# ASM2021.net
KiCad netlist of a schematic drawn in EAGLE
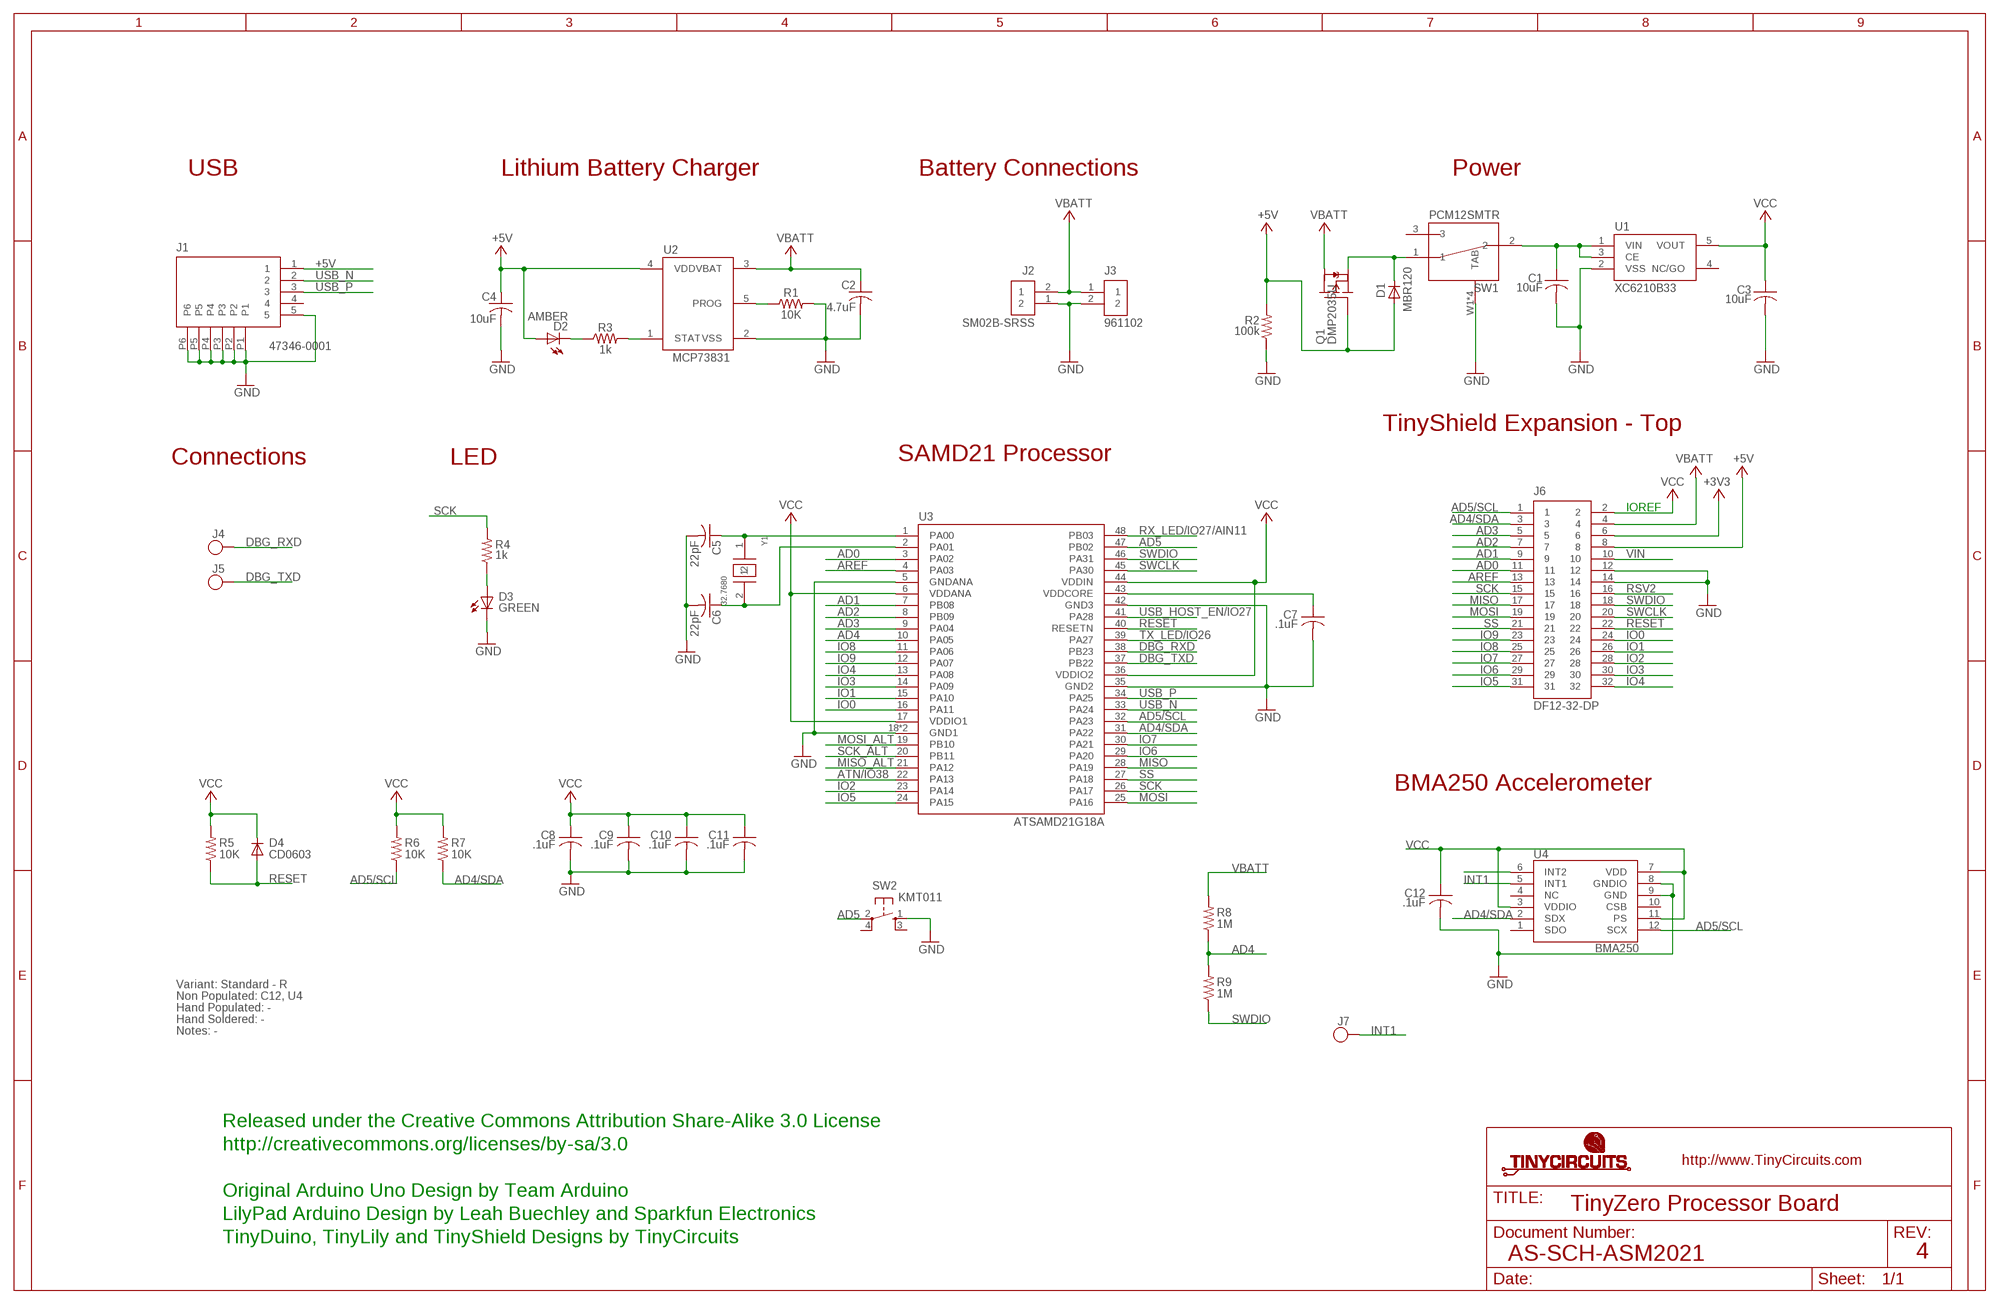
[diagram p0: schematic, sheet 1]

(export (version "E")
  (design (tool "Eeschema 10.0.6"))
  (components
    (comp (ref "C1")
      (value "10uF")
      (footprint "eagle-import:C0603")
      (fields (field (name "PARTNO") "AS-ITM-00002") (field (name "PARTNO_1") "AS-ITM-00002"))
      (libsource (lib "eagle-import") (part "AS-ITM-00002"))
    )
    (comp (ref "C2")
      (value "4.7uF")
      (footprint "eagle-import:C0603")
      (fields (field (name "PARTNO") "AS-ITM-00088") (field (name "PARTNO_1") "AS-ITM-00088"))
      (libsource (lib "eagle-import") (part "AS-ITM-00088"))
    )
    (comp (ref "C3")
      (value "10uF")
      (footprint "eagle-import:C0603")
      (fields (field (name "PARTNO") "AS-ITM-00002") (field (name "PARTNO_1") "AS-ITM-00002"))
      (libsource (lib "eagle-import") (part "AS-ITM-00002"))
    )
    (comp (ref "C4")
      (value "10uF")
      (footprint "eagle-import:C0603")
      (fields (field (name "PARTNO") "AS-ITM-00002") (field (name "PARTNO_1") "AS-ITM-00002"))
      (libsource (lib "eagle-import") (part "AS-ITM-00002"))
    )
    (comp (ref "C5")
      (value "22pF")
      (footprint "eagle-import:C0402")
      (fields (field (name "PARTNO") "AS-ITM-00211") (field (name "PARTNO_1") "AS-ITM-00211"))
      (libsource (lib "eagle-import") (part "AS-ITM-00211"))
    )
    (comp (ref "C6")
      (value "22pF")
      (footprint "eagle-import:C0402")
      (fields (field (name "PARTNO") "AS-ITM-00211") (field (name "PARTNO_1") "AS-ITM-00211"))
      (libsource (lib "eagle-import") (part "AS-ITM-00211"))
    )
    (comp (ref "C7")
      (value ".1uF")
      (footprint "eagle-import:C0402")
      (fields (field (name "PARTNO") "AS-ITM-00008") (field (name "PARTNO_1") "AS-ITM-00008"))
      (libsource (lib "eagle-import") (part "AS-ITM-00008"))
    )
    (comp (ref "C8")
      (value ".1uF")
      (footprint "eagle-import:C0402")
      (fields (field (name "PARTNO") "AS-ITM-00008") (field (name "PARTNO_1") "AS-ITM-00008"))
      (libsource (lib "eagle-import") (part "AS-ITM-00008"))
    )
    (comp (ref "C9")
      (value ".1uF")
      (footprint "eagle-import:C0402")
      (fields (field (name "PARTNO") "AS-ITM-00008") (field (name "PARTNO_1") "AS-ITM-00008"))
      (libsource (lib "eagle-import") (part "AS-ITM-00008"))
    )
    (comp (ref "C10")
      (value ".1uF")
      (footprint "eagle-import:C0402")
      (fields (field (name "PARTNO") "AS-ITM-00008") (field (name "PARTNO_1") "AS-ITM-00008"))
      (libsource (lib "eagle-import") (part "AS-ITM-00008"))
    )
    (comp (ref "C11")
      (value ".1uF")
      (footprint "eagle-import:C0402")
      (fields (field (name "PARTNO") "AS-ITM-00008") (field (name "PARTNO_1") "AS-ITM-00008"))
      (libsource (lib "eagle-import") (part "AS-ITM-00008"))
    )
    (comp (ref "C12")
      (value ".1uF")
      (footprint "eagle-import:C0402")
      (fields (field (name "PARTNO") "AS-ITM-00008") (field (name "PARTNO_1") "AS-ITM-00008"))
      (libsource (lib "eagle-import") (part "AS-ITM-00008"))
    )
    (comp (ref "D1")
      (value "MBR120")
      (footprint "eagle-import:SOD-123FL")
      (fields (field (name "PARTNO") "AS-ITM-00111"))
      (libsource (lib "eagle-import") (part "AS-ITM-00111"))
    )
    (comp (ref "D2")
      (value "AMBER")
      (footprint "eagle-import:LNJ_LED")
      (fields (field (name "PARTNO") "AS-ITM-00026") (field (name "PARTNO_1") "AS-ITM-00026"))
      (libsource (lib "eagle-import") (part "AS-ITM-00026"))
    )
    (comp (ref "D3")
      (value "GREEN")
      (footprint "eagle-import:LNJ_LED")
      (fields (field (name "PARTNO") "AS-ITM-00011") (field (name "PARTNO_1") "AS-ITM-00011"))
      (libsource (lib "eagle-import") (part "AS-ITM-00011"))
    )
    (comp (ref "D4")
      (value "CD0603")
      (footprint "eagle-import:0603")
      (fields (field (name "PARTNO") "AS-ITM-00009") (field (name "PARTNO_1") "AS-ITM-00009"))
      (libsource (lib "eagle-import") (part "AS-ITM-00009"))
    )
    (comp (ref "J1")
      (value "47346-0001")
      (footprint "eagle-import:MICRO_USB")
      (fields (field (name "PARTNO") "AS-ITM-00021"))
      (libsource (lib "eagle-import") (part "AS-ITM-00021"))
    )
    (comp (ref "J2")
      (value "SM02B-SRSS")
      (footprint "eagle-import:JST_SH_2X1")
      (fields (field (name "PARTNO") "AS-ITM-00231"))
      (libsource (lib "eagle-import") (part "AS-ITM-00231"))
    )
    (comp (ref "J3")
      (value "961102")
      (footprint "eagle-import:2X.1_")
      (fields (field (name "PARTNO") "AS-ITM-00044"))
      (libsource (lib "eagle-import") (part "AS-ITM-00044"))
    )
    (comp (ref "J4")
      (value "TEST_POINT")
      (footprint "eagle-import:TEST_POINT_1MM")
      (libsource (lib "eagle-import") (part "TEST_POINT"))
    )
    (comp (ref "J5")
      (value "TEST_POINT")
      (footprint "eagle-import:TEST_POINT_1MM")
      (libsource (lib "eagle-import") (part "TEST_POINT"))
    )
    (comp (ref "J6")
      (value "DF12-32-DP")
      (footprint "eagle-import:DF12-32-DP")
      (fields (field (name "PARTNO") "AS-ITM-00015") (field (name "PARTNO_1") "AS-ITM-00015"))
      (libsource (lib "eagle-import") (part "AS-ITM-00015"))
    )
    (comp (ref "J7")
      (value "TEST_POINT")
      (footprint "eagle-import:TEST_POINT_1MM")
      (libsource (lib "eagle-import") (part "TEST_POINT"))
    )
    (comp (ref "Q1")
      (value "DMP2035U")
      (footprint "eagle-import:SOT23")
      (fields (field (name "PARTNO") "AS-ITM-00024"))
      (libsource (lib "eagle-import") (part "AS-ITM-00024"))
    )
    (comp (ref "R1")
      (value "10K")
      (footprint "eagle-import:0402")
      (fields (field (name "PARTNO") "AS-ITM-00032"))
      (libsource (lib "eagle-import") (part "AS-ITM-00032"))
    )
    (comp (ref "R2")
      (value "100k")
      (footprint "eagle-import:0402")
      (fields (field (name "PARTNO") "AS-ITM-00004") (field (name "PARTNO_1") "AS-ITM-00004"))
      (libsource (lib "eagle-import") (part "AS-ITM-00004"))
    )
    (comp (ref "R3")
      (value "1k")
      (footprint "eagle-import:0402")
      (fields (field (name "PARTNO") "AS-ITM-00003") (field (name "PARTNO_1") "AS-ITM-00003"))
      (libsource (lib "eagle-import") (part "AS-ITM-00003"))
    )
    (comp (ref "R4")
      (value "1k")
      (footprint "eagle-import:0402")
      (fields (field (name "PARTNO") "AS-ITM-00003") (field (name "PARTNO_1") "AS-ITM-00003"))
      (libsource (lib "eagle-import") (part "AS-ITM-00003"))
    )
    (comp (ref "R5")
      (value "10K")
      (footprint "eagle-import:0402")
      (fields (field (name "PARTNO") "AS-ITM-00032") (field (name "PARTNO_1") "AS-ITM-00032"))
      (libsource (lib "eagle-import") (part "AS-ITM-00032"))
    )
    (comp (ref "R6")
      (value "10K")
      (footprint "eagle-import:0402")
      (fields (field (name "PARTNO") "AS-ITM-00032") (field (name "PARTNO_1") "AS-ITM-00032"))
      (libsource (lib "eagle-import") (part "AS-ITM-00032"))
    )
    (comp (ref "R7")
      (value "10K")
      (footprint "eagle-import:0402")
      (fields (field (name "PARTNO") "AS-ITM-00032") (field (name "PARTNO_1") "AS-ITM-00032"))
      (libsource (lib "eagle-import") (part "AS-ITM-00032"))
    )
    (comp (ref "R8")
      (value "1M")
      (footprint "eagle-import:0402")
      (fields (field (name "PARTNO") "AS-ITM-00005") (field (name "PARTNO_1") "AS-ITM-00005"))
      (libsource (lib "eagle-import") (part "AS-ITM-00005"))
    )
    (comp (ref "R9")
      (value "1M")
      (footprint "eagle-import:0402")
      (fields (field (name "PARTNO") "AS-ITM-00005") (field (name "PARTNO_1") "AS-ITM-00005"))
      (libsource (lib "eagle-import") (part "AS-ITM-00005"))
    )
    (comp (ref "SW1")
      (value "PCM12SMTR")
      (footprint "eagle-import:PCM12SMTR")
      (fields (field (name "PARTNO") "AS-ITM-00220"))
      (libsource (lib "eagle-import") (part "AS-ITM-00220"))
    )
    (comp (ref "SW2")
      (value "KMT011")
      (footprint "eagle-import:KMT011")
      (fields (field (name "PARTNO") "AS-ITM-00041"))
      (libsource (lib "eagle-import") (part "AS-ITM-00041"))
    )
    (comp (ref "U1")
      (value "XC6210B33")
      (footprint "eagle-import:SOT-25")
      (fields (field (name "PARTNO") "AS-ITM-00046"))
      (libsource (lib "eagle-import") (part "AS-ITM-00046"))
    )
    (comp (ref "U2")
      (value "MCP73831")
      (footprint "eagle-import:SOT-23")
      (fields (field (name "PARTNO") "AS-ITM-00136"))
      (libsource (lib "eagle-import") (part "AS-ITM-00136"))
    )
    (comp (ref "U3")
      (value "ATSAMD21G18A")
      (footprint "eagle-import:QFN48")
      (fields (field (name "PARTNO") "AS-ITM-00273") (field (name "PARTNO_1") "AS-ITM-00273"))
      (libsource (lib "eagle-import") (part "AS-ITM-00273"))
    )
    (comp (ref "U4")
      (value "BMA250")
      (footprint "eagle-import:3-AXIS_ACCELEROMETER")
      (fields (field (name "PARTNO") "AS-ITM-00070"))
      (libsource (lib "eagle-import") (part "AS-ITM-00070"))
    )
    (comp (ref "Y1")
      (value "32.7680")
      (footprint "eagle-import:ABS06")
      (fields (field (name "PARTNO") "AS-ITM-00279") (field (name "PARTNO_1") "AS-ITM-00279"))
      (libsource (lib "eagle-import") (part "AS-ITM-00279"))
    )
  )
  (nets
    (net (code "1") (name "+3V3") (class "Default")
      (node (ref "J6") (pin "6") (pinfunction "6_6") (pintype "bidirectional"))
    )
    (net (code "2") (name "+5V") (class "Default")
      (node (ref "C4") (pin "1") (pinfunction "1_1") (pintype "passive"))
      (node (ref "D1") (pin "A") (pinfunction "A_A") (pintype "passive"))
      (node (ref "D2") (pin "A") (pinfunction "A_A") (pintype "passive"))
      (node (ref "J1") (pin "1") (pinfunction "1_1") (pintype "bidirectional"))
      (node (ref "J6") (pin "8") (pinfunction "8_8") (pintype "bidirectional"))
      (node (ref "Q1") (pin "B") (pinfunction "G_B") (pintype "passive"))
      (node (ref "R2") (pin "2") (pinfunction "2_2") (pintype "passive"))
      (node (ref "U2") (pin "4") (pinfunction "VDD_4") (pintype "bidirectional"))
    )
    (net (code "3") (name "/AD0") (class "Default")
      (node (ref "J6") (pin "11") (pinfunction "11_11") (pintype "bidirectional"))
      (node (ref "U3") (pin "3") (pinfunction "PA02_3") (pintype "bidirectional"))
    )
    (net (code "4") (name "/AD1") (class "Default")
      (node (ref "J6") (pin "9") (pinfunction "9_9") (pintype "bidirectional"))
      (node (ref "U3") (pin "7") (pinfunction "PB08_7") (pintype "bidirectional"))
    )
    (net (code "5") (name "/AD2") (class "Default")
      (node (ref "J6") (pin "7") (pinfunction "7_7") (pintype "bidirectional"))
      (node (ref "U3") (pin "8") (pinfunction "PB09_8") (pintype "bidirectional"))
    )
    (net (code "6") (name "/AD3") (class "Default")
      (node (ref "J6") (pin "5") (pinfunction "5_5") (pintype "bidirectional"))
      (node (ref "U3") (pin "9") (pinfunction "PA04_9") (pintype "bidirectional"))
    )
    (net (code "7") (name "/AD4") (class "Default")
      (node (ref "R8") (pin "1") (pinfunction "1_1") (pintype "passive"))
      (node (ref "R9") (pin "2") (pinfunction "2_2") (pintype "passive"))
      (node (ref "U3") (pin "10") (pinfunction "PA05_10") (pintype "bidirectional"))
    )
    (net (code "8") (name "/AD4{slash}SDA") (class "Default")
      (node (ref "J6") (pin "3") (pinfunction "3_3") (pintype "bidirectional"))
      (node (ref "R7") (pin "1") (pinfunction "1_1") (pintype "passive"))
      (node (ref "U3") (pin "31") (pinfunction "PA22_31") (pintype "bidirectional"))
      (node (ref "U4") (pin "2") (pinfunction "SDX_2") (pintype "bidirectional"))
    )
    (net (code "9") (name "/AD5") (class "Default")
      (node (ref "SW2") (pin "2") (pinfunction "2_2") (pintype "passive"))
      (node (ref "U3") (pin "47") (pinfunction "PB02_47") (pintype "bidirectional"))
    )
    (net (code "10") (name "/AD5{slash}SCL") (class "Default")
      (node (ref "J6") (pin "1") (pinfunction "1_1") (pintype "bidirectional"))
      (node (ref "R6") (pin "1") (pinfunction "1_1") (pintype "passive"))
      (node (ref "U3") (pin "32") (pinfunction "PA23_32") (pintype "bidirectional"))
      (node (ref "U4") (pin "12") (pinfunction "SCX_12") (pintype "bidirectional"))
    )
    (net (code "11") (name "/AREF") (class "Default")
      (node (ref "J6") (pin "13") (pinfunction "13_13") (pintype "bidirectional"))
      (node (ref "U3") (pin "4") (pinfunction "PA03_4") (pintype "bidirectional"))
    )
    (net (code "12") (name "/ATN{slash}IO38") (class "Default")
      (node (ref "U3") (pin "22") (pinfunction "PA13_22") (pintype "bidirectional"))
    )
    (net (code "13") (name "/DBG_RXD") (class "Default")
      (node (ref "J4") (pin "P$1") (pinfunction "1_P$1") (pintype "bidirectional"))
      (node (ref "U3") (pin "38") (pinfunction "PB23_38") (pintype "bidirectional"))
    )
    (net (code "14") (name "/DBG_TXD") (class "Default")
      (node (ref "J5") (pin "P$1") (pinfunction "1_P$1") (pintype "bidirectional"))
      (node (ref "U3") (pin "37") (pinfunction "PB22_37") (pintype "bidirectional"))
    )
    (net (code "15") (name "/INT1") (class "Default")
      (node (ref "J7") (pin "P$1") (pinfunction "1_P$1") (pintype "bidirectional"))
      (node (ref "U4") (pin "5") (pinfunction "INT1_5") (pintype "bidirectional"))
    )
    (net (code "16") (name "/IO0") (class "Default")
      (node (ref "J6") (pin "24") (pinfunction "24_24") (pintype "bidirectional"))
      (node (ref "U3") (pin "16") (pinfunction "PA11_16") (pintype "bidirectional"))
    )
    (net (code "17") (name "/IO1") (class "Default")
      (node (ref "J6") (pin "26") (pinfunction "26_26") (pintype "bidirectional"))
      (node (ref "U3") (pin "15") (pinfunction "PA10_15") (pintype "bidirectional"))
    )
    (net (code "18") (name "/IO2") (class "Default")
      (node (ref "J6") (pin "28") (pinfunction "28_28") (pintype "bidirectional"))
      (node (ref "U3") (pin "23") (pinfunction "PA14_23") (pintype "bidirectional"))
    )
    (net (code "19") (name "/IO3") (class "Default")
      (node (ref "J6") (pin "30") (pinfunction "30_30") (pintype "bidirectional"))
      (node (ref "U3") (pin "14") (pinfunction "PA09_14") (pintype "bidirectional"))
    )
    (net (code "20") (name "/IO4") (class "Default")
      (node (ref "J6") (pin "32") (pinfunction "32_32") (pintype "bidirectional"))
      (node (ref "U3") (pin "13") (pinfunction "PA08_13") (pintype "bidirectional"))
    )
    (net (code "21") (name "/IO5") (class "Default")
      (node (ref "J6") (pin "31") (pinfunction "31_31") (pintype "bidirectional"))
      (node (ref "U3") (pin "24") (pinfunction "PA15_24") (pintype "bidirectional"))
    )
    (net (code "22") (name "/IO6") (class "Default")
      (node (ref "J6") (pin "29") (pinfunction "29_29") (pintype "bidirectional"))
      (node (ref "U3") (pin "29") (pinfunction "PA20_29") (pintype "bidirectional"))
    )
    (net (code "23") (name "/IO7") (class "Default")
      (node (ref "J6") (pin "27") (pinfunction "27_27") (pintype "bidirectional"))
      (node (ref "U3") (pin "30") (pinfunction "PA21_30") (pintype "bidirectional"))
    )
    (net (code "24") (name "/IO8") (class "Default")
      (node (ref "J6") (pin "25") (pinfunction "25_25") (pintype "bidirectional"))
      (node (ref "U3") (pin "11") (pinfunction "PA06_11") (pintype "bidirectional"))
    )
    (net (code "25") (name "/IO9") (class "Default")
      (node (ref "J6") (pin "23") (pinfunction "23_23") (pintype "bidirectional"))
      (node (ref "U3") (pin "12") (pinfunction "PA07_12") (pintype "bidirectional"))
    )
    (net (code "26") (name "/MISO") (class "Default")
      (node (ref "J6") (pin "17") (pinfunction "17_17") (pintype "bidirectional"))
      (node (ref "U3") (pin "28") (pinfunction "PA19_28") (pintype "bidirectional"))
    )
    (net (code "27") (name "/MISO_ALT") (class "Default")
      (node (ref "U3") (pin "21") (pinfunction "PA12_21") (pintype "bidirectional"))
    )
    (net (code "28") (name "/MOSI") (class "Default")
      (node (ref "J6") (pin "19") (pinfunction "19_19") (pintype "bidirectional"))
      (node (ref "U3") (pin "25") (pinfunction "PA16_25") (pintype "bidirectional"))
    )
    (net (code "29") (name "/MOSI_ALT") (class "Default")
      (node (ref "U3") (pin "19") (pinfunction "PB10_19") (pintype "bidirectional"))
    )
    (net (code "30") (name "/RESET") (class "Default")
      (node (ref "D4") (pin "A") (pinfunction "A_A") (pintype "passive"))
      (node (ref "J6") (pin "22") (pinfunction "22_22") (pintype "bidirectional"))
      (node (ref "R5") (pin "1") (pinfunction "1_1") (pintype "passive"))
      (node (ref "U3") (pin "40") (pinfunction "RESETN_40") (pintype "bidirectional"))
    )
    (net (code "31") (name "/RSV2") (class "Default")
      (node (ref "J6") (pin "16") (pinfunction "16_16") (pintype "bidirectional"))
    )
    (net (code "32") (name "/RX_LED{slash}IO27{slash}AIN11") (class "Default")
      (node (ref "U3") (pin "48") (pinfunction "PB03_48") (pintype "bidirectional"))
    )
    (net (code "33") (name "/SCK") (class "Default")
      (node (ref "J6") (pin "15") (pinfunction "15_15") (pintype "bidirectional"))
      (node (ref "R4") (pin "2") (pinfunction "2_2") (pintype "passive"))
      (node (ref "U3") (pin "26") (pinfunction "PA17_26") (pintype "bidirectional"))
    )
    (net (code "34") (name "/SCK_ALT") (class "Default")
      (node (ref "U3") (pin "20") (pinfunction "PB11_20") (pintype "bidirectional"))
    )
    (net (code "35") (name "/SS") (class "Default")
      (node (ref "J6") (pin "21") (pinfunction "21_21") (pintype "bidirectional"))
      (node (ref "U3") (pin "27") (pinfunction "PA18_27") (pintype "bidirectional"))
    )
    (net (code "36") (name "/SWCLK") (class "Default")
      (node (ref "J6") (pin "20") (pinfunction "20_20") (pintype "bidirectional"))
      (node (ref "U3") (pin "45") (pinfunction "PA30_45") (pintype "bidirectional"))
    )
    (net (code "37") (name "/SWDIO") (class "Default")
      (node (ref "J6") (pin "18") (pinfunction "18_18") (pintype "bidirectional"))
      (node (ref "R9") (pin "1") (pinfunction "1_1") (pintype "passive"))
      (node (ref "U3") (pin "46") (pinfunction "PA31_46") (pintype "bidirectional"))
    )
    (net (code "38") (name "/TX_LED{slash}IO26") (class "Default")
      (node (ref "U3") (pin "39") (pinfunction "PA27_39") (pintype "bidirectional"))
    )
    (net (code "39") (name "/USB_HOST_EN{slash}IO27") (class "Default")
      (node (ref "U3") (pin "41") (pinfunction "PA28_41") (pintype "bidirectional"))
    )
    (net (code "40") (name "/USB_N") (class "Default")
      (node (ref "J1") (pin "2") (pinfunction "2_2") (pintype "bidirectional"))
      (node (ref "U3") (pin "33") (pinfunction "PA24_33") (pintype "bidirectional"))
    )
    (net (code "41") (name "/USB_P") (class "Default")
      (node (ref "J1") (pin "3") (pinfunction "3_3") (pintype "bidirectional"))
      (node (ref "U3") (pin "34") (pinfunction "PA25_34") (pintype "bidirectional"))
    )
    (net (code "42") (name "/VIN") (class "Default")
      (node (ref "J6") (pin "10") (pinfunction "10_10") (pintype "bidirectional"))
    )
    (net (code "43") (name "GND") (class "Default")
      (node (ref "C1") (pin "2") (pinfunction "2_2") (pintype "passive"))
      (node (ref "C10") (pin "2") (pinfunction "2_2") (pintype "passive"))
      (node (ref "C11") (pin "2") (pinfunction "2_2") (pintype "passive"))
      (node (ref "C12") (pin "2") (pinfunction "2_2") (pintype "passive"))
      (node (ref "C2") (pin "2") (pinfunction "2_2") (pintype "passive"))
      (node (ref "C3") (pin "2") (pinfunction "2_2") (pintype "passive"))
      (node (ref "C4") (pin "2") (pinfunction "2_2") (pintype "passive"))
      (node (ref "C5") (pin "2") (pinfunction "2_2") (pintype "passive"))
      (node (ref "C6") (pin "2") (pinfunction "2_2") (pintype "passive"))
      (node (ref "C7") (pin "2") (pinfunction "2_2") (pintype "passive"))
      (node (ref "C8") (pin "2") (pinfunction "2_2") (pintype "passive"))
      (node (ref "C9") (pin "2") (pinfunction "2_2") (pintype "passive"))
      (node (ref "D3") (pin "C") (pinfunction "C_C") (pintype "passive"))
      (node (ref "J1") (pin "5") (pinfunction "5_5") (pintype "bidirectional"))
      (node (ref "J1") (pin "P1") (pinfunction "P1_P1") (pintype "bidirectional"))
      (node (ref "J1") (pin "P2") (pinfunction "P2_P2") (pintype "bidirectional"))
      (node (ref "J1") (pin "P3") (pinfunction "P3_P3") (pintype "bidirectional"))
      (node (ref "J1") (pin "P4") (pinfunction "P4_P4") (pintype "bidirectional"))
      (node (ref "J1") (pin "P5") (pinfunction "P5_P5") (pintype "bidirectional"))
      (node (ref "J1") (pin "P6") (pinfunction "P6_P6") (pintype "bidirectional"))
      (node (ref "J2") (pin "1") (pinfunction "2_1") (pintype "bidirectional"))
      (node (ref "J3") (pin "2") (pinfunction "2_2") (pintype "bidirectional"))
      (node (ref "J6") (pin "12") (pinfunction "12_12") (pintype "bidirectional"))
      (node (ref "J6") (pin "14") (pinfunction "14_14") (pintype "bidirectional"))
      (node (ref "R1") (pin "2") (pinfunction "2_2") (pintype "passive"))
      (node (ref "R2") (pin "1") (pinfunction "1_1") (pintype "passive"))
      (node (ref "SW1") (pin "W1") (pinfunction "TAB_W1") (pintype "bidirectional"))
      (node (ref "SW1") (pin "W2") (pinfunction "TAB_W2") (pintype "bidirectional"))
      (node (ref "SW1") (pin "W3") (pinfunction "TAB_W3") (pintype "bidirectional"))
      (node (ref "SW1") (pin "W4") (pinfunction "TAB_W4") (pintype "bidirectional"))
      (node (ref "SW2") (pin "1") (pinfunction "1_1") (pintype "passive"))
      (node (ref "U1") (pin "2") (pinfunction "VSS_2") (pintype "power_in"))
      (node (ref "U2") (pin "2") (pinfunction "VSS_2") (pintype "bidirectional"))
      (node (ref "U3") (pin "18") (pinfunction "GND1_18") (pintype "bidirectional"))
      (node (ref "U3") (pin "35") (pinfunction "GND2_35") (pintype "bidirectional"))
      (node (ref "U3") (pin "42") (pinfunction "GND3_42") (pintype "bidirectional"))
      (node (ref "U3") (pin "5") (pinfunction "GNDANA_5") (pintype "bidirectional"))
      (node (ref "U3") (pin "EXP") (pinfunction "GND1_EXP") (pintype "bidirectional"))
      (node (ref "U4") (pin "8") (pinfunction "GNDIO_8") (pintype "bidirectional"))
      (node (ref "U4") (pin "9") (pinfunction "GND_9") (pintype "bidirectional"))
    )
    (net (code "44") (name "Net-(D2-PadC)") (class "Default")
      (node (ref "D2") (pin "C") (pinfunction "C_C") (pintype "passive"))
      (node (ref "R3") (pin "1") (pinfunction "1_1") (pintype "passive"))
    )
    (net (code "45") (name "Net-(D3-PadA)") (class "Default")
      (node (ref "D3") (pin "A") (pinfunction "A_A") (pintype "passive"))
      (node (ref "R4") (pin "1") (pinfunction "1_1") (pintype "passive"))
    )
    (net (code "46") (name "Net-(Q1-S)") (class "Default")
      (node (ref "D1") (pin "C") (pinfunction "C_C") (pintype "passive"))
      (node (ref "Q1") (pin "E") (pinfunction "S_E") (pintype "passive"))
      (node (ref "SW1") (pin "1") (pinfunction "1_1") (pintype "bidirectional"))
    )
    (net (code "47") (name "Net-(U1-CE)") (class "Default")
      (node (ref "C1") (pin "1") (pinfunction "1_1") (pintype "passive"))
      (node (ref "SW1") (pin "2") (pinfunction "2_2") (pintype "bidirectional"))
      (node (ref "U1") (pin "1") (pinfunction "VIN_1") (pintype "bidirectional"))
      (node (ref "U1") (pin "3") (pinfunction "CE_3") (pintype "bidirectional"))
    )
    (net (code "48") (name "Net-(U2-PROG)") (class "Default")
      (node (ref "R1") (pin "1") (pinfunction "1_1") (pintype "passive"))
      (node (ref "U2") (pin "5") (pinfunction "PROG_5") (pintype "bidirectional"))
    )
    (net (code "49") (name "Net-(U2-STAT)") (class "Default")
      (node (ref "R3") (pin "2") (pinfunction "2_2") (pintype "passive"))
      (node (ref "U2") (pin "1") (pinfunction "STAT_1") (pintype "bidirectional"))
    )
    (net (code "50") (name "Net-(U3-PA00)") (class "Default")
      (node (ref "C5") (pin "1") (pinfunction "1_1") (pintype "passive"))
      (node (ref "U3") (pin "1") (pinfunction "PA00_1") (pintype "bidirectional"))
      (node (ref "Y1") (pin "1") (pinfunction "1_1") (pintype "bidirectional"))
    )
    (net (code "51") (name "Net-(U3-PA01)") (class "Default")
      (node (ref "C6") (pin "1") (pinfunction "1_1") (pintype "passive"))
      (node (ref "U3") (pin "2") (pinfunction "PA01_2") (pintype "bidirectional"))
      (node (ref "Y1") (pin "2") (pinfunction "2_2") (pintype "bidirectional"))
    )
    (net (code "52") (name "Net-(U3-VDDCORE)") (class "Default")
      (node (ref "C7") (pin "1") (pinfunction "1_1") (pintype "passive"))
      (node (ref "U3") (pin "43") (pinfunction "VDDCORE_43") (pintype "bidirectional"))
    )
    (net (code "53") (name "VBATT") (class "Default")
      (node (ref "C2") (pin "1") (pinfunction "1_1") (pintype "passive"))
      (node (ref "J2") (pin "2") (pinfunction "1_2") (pintype "bidirectional"))
      (node (ref "J3") (pin "1") (pinfunction "1_1") (pintype "bidirectional"))
      (node (ref "J6") (pin "4") (pinfunction "4_4") (pintype "bidirectional"))
      (node (ref "Q1") (pin "C") (pinfunction "D_C") (pintype "passive"))
      (node (ref "R8") (pin "2") (pinfunction "2_2") (pintype "passive"))
      (node (ref "U2") (pin "3") (pinfunction "VBAT_3") (pintype "bidirectional"))
    )
    (net (code "54") (name "VCC") (class "Default")
      (node (ref "C10") (pin "1") (pinfunction "1_1") (pintype "passive"))
      (node (ref "C11") (pin "1") (pinfunction "1_1") (pintype "passive"))
      (node (ref "C12") (pin "1") (pinfunction "1_1") (pintype "passive"))
      (node (ref "C3") (pin "1") (pinfunction "1_1") (pintype "passive"))
      (node (ref "C8") (pin "1") (pinfunction "1_1") (pintype "passive"))
      (node (ref "C9") (pin "1") (pinfunction "1_1") (pintype "passive"))
      (node (ref "D4") (pin "C") (pinfunction "C_C") (pintype "passive"))
      (node (ref "J6") (pin "2") (pinfunction "2_2") (pintype "bidirectional"))
      (node (ref "R5") (pin "2") (pinfunction "2_2") (pintype "passive"))
      (node (ref "R6") (pin "2") (pinfunction "2_2") (pintype "passive"))
      (node (ref "R7") (pin "2") (pinfunction "2_2") (pintype "passive"))
      (node (ref "U1") (pin "5") (pinfunction "VOUT_5") (pintype "bidirectional"))
      (node (ref "U3") (pin "17") (pinfunction "VDDIO1_17") (pintype "bidirectional"))
      (node (ref "U3") (pin "36") (pinfunction "VDDIO2_36") (pintype "bidirectional"))
      (node (ref "U3") (pin "44") (pinfunction "VDDIN_44") (pintype "bidirectional"))
      (node (ref "U3") (pin "6") (pinfunction "VDDANA_6") (pintype "bidirectional"))
      (node (ref "U4") (pin "11") (pinfunction "PS_11") (pintype "bidirectional"))
      (node (ref "U4") (pin "3") (pinfunction "VDDIO_3") (pintype "bidirectional"))
      (node (ref "U4") (pin "7") (pinfunction "VDD_7") (pintype "bidirectional"))
    )
    (net (code "55") (name "unconnected-(J1-Pad4)") (class "Default")
      (node (ref "J1") (pin "4") (pinfunction "4_4") (pintype "bidirectional"))
    )
    (net (code "56") (name "unconnected-(SW1-Pad3)") (class "Default")
      (node (ref "SW1") (pin "3") (pinfunction "3_3") (pintype "bidirectional"))
    )
    (net (code "57") (name "unconnected-(SW2-Pad3)") (class "Default")
      (node (ref "SW2") (pin "3") (pinfunction "3_3") (pintype "passive"))
    )
    (net (code "58") (name "unconnected-(SW2-Pad4)") (class "Default")
      (node (ref "SW2") (pin "4") (pinfunction "4_4") (pintype "passive"))
    )
    (net (code "59") (name "unconnected-(U1-NC{slash}GO-Pad4)") (class "Default")
      (node (ref "U1") (pin "4") (pinfunction "NC/GO_4") (pintype "bidirectional"))
    )
    (net (code "60") (name "unconnected-(U4-CSB-Pad10)") (class "Default")
      (node (ref "U4") (pin "10") (pinfunction "CSB_10") (pintype "bidirectional"))
    )
    (net (code "61") (name "unconnected-(U4-INT2-Pad6)") (class "Default")
      (node (ref "U4") (pin "6") (pinfunction "INT2_6") (pintype "bidirectional"))
    )
    (net (code "62") (name "unconnected-(U4-NC-Pad4)") (class "Default")
      (node (ref "U4") (pin "4") (pinfunction "NC_4") (pintype "bidirectional"))
    )
    (net (code "63") (name "unconnected-(U4-SDO-Pad1)") (class "Default")
      (node (ref "U4") (pin "1") (pinfunction "SDO_1") (pintype "bidirectional"))
    )
  )
)
